# MC21R01_EtherCAT.net
KiCad netlist of a schematic drawn in Altium Designer
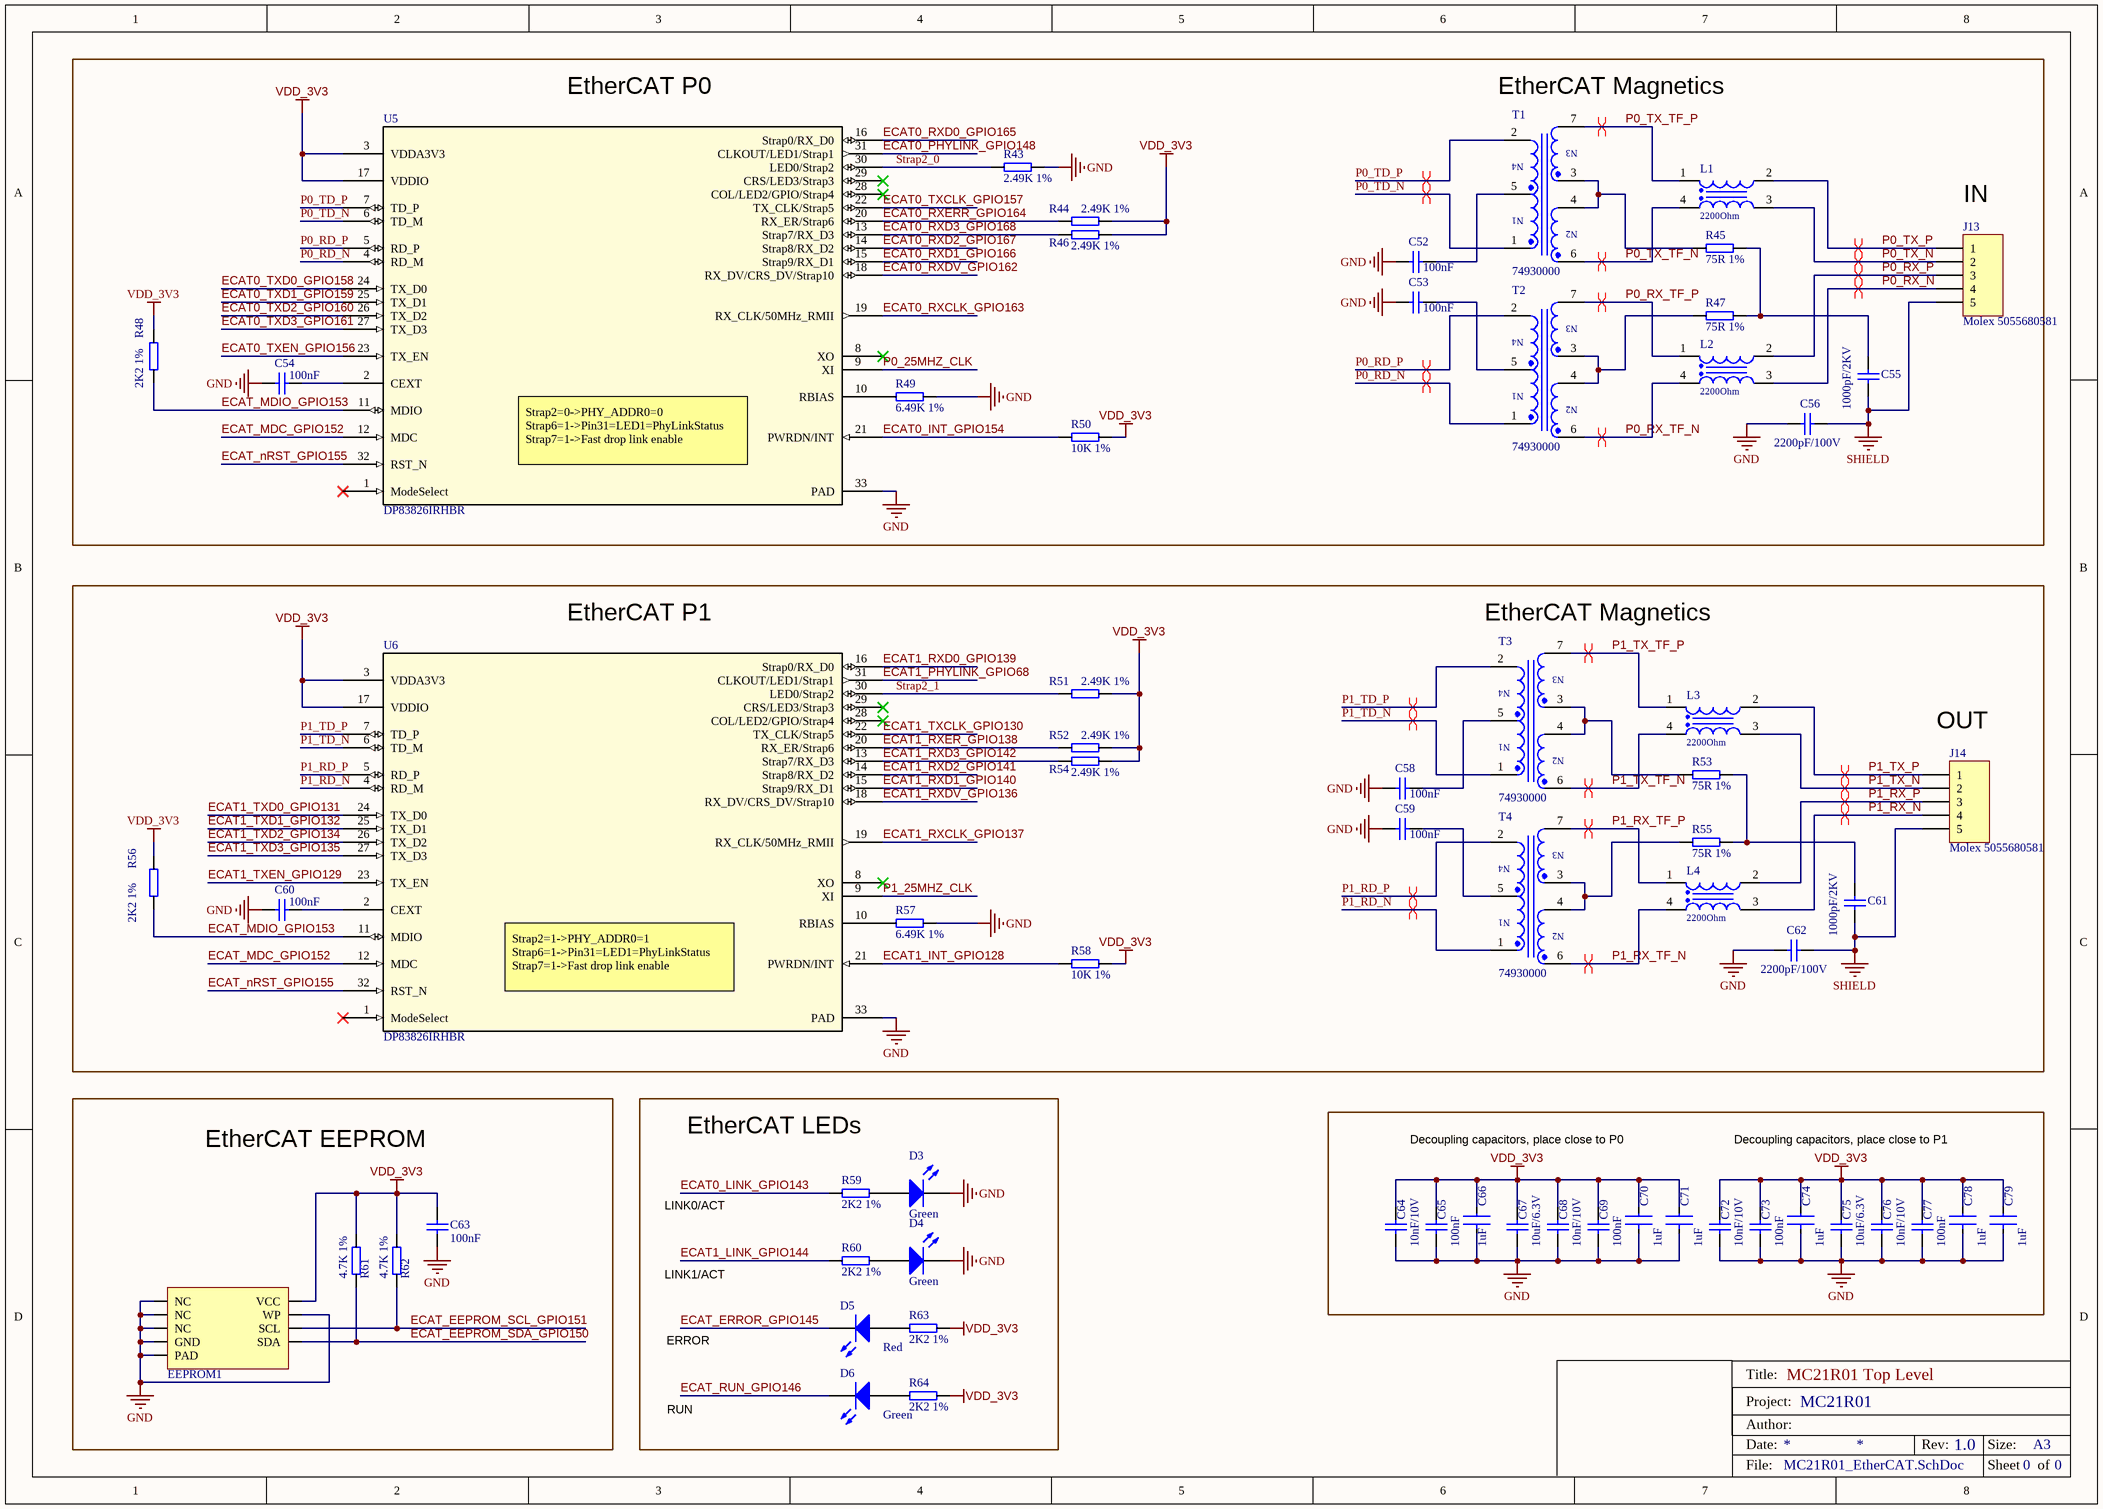
[diagram p0: MC21R01_EtherCAT.SchDoc]

(export (version "E")
  (design (tool "Eeschema 10.0.6"))
  (components
    (comp (ref "C52")
      (value "100nF")
      (footprint "CAPC0603X03N")
      (description "100nF/25V 0201 10% Tolerance X6S Multilayer Ceramic Chip Capacitor")
      (fields (field (name "TOLERANCE") "10%") (field (name "Comment") "100nF/25V 0201 10% X6S"))
      (libsource (lib "Wandercraft") (part "STD_CAP_2PIN_NPOL"))
    )
    (comp (ref "C53")
      (value "100nF")
      (footprint "CAPC0603X03N")
      (description "100nF/25V 0201 10% Tolerance X6S Multilayer Ceramic Chip Capacitor")
      (fields (field (name "TOLERANCE") "10%") (field (name "Comment") "100nF/25V 0201 10% X6S"))
      (libsource (lib "Wandercraft") (part "STD_CAP_2PIN_NPOL"))
    )
    (comp (ref "C54")
      (value "100nF")
      (footprint "CAPC0603X03N")
      (description "100nF/25V 0201 10% Tolerance X6S Multilayer Ceramic Chip Capacitor")
      (fields (field (name "TOLERANCE") "10%") (field (name "Comment") "100nF/25V 0201 10% X6S"))
      (libsource (lib "Wandercraft") (part "STD_CAP_2PIN_NPOL"))
    )
    (comp (ref "C55")
      (value "1000pF/2KV")
      (footprint "PAL_Capacitors:1206 SMD Capacitor")
      (description "1000 pF 2 KV 1206  ±10% Tolerance X7R Multilayer Ceramic Chip Capacitor")
      (libsource (lib "PAL_Capacitors") (part "1000pF/2KV 1206 10% X7R"))
    )
    (comp (ref "C56")
      (value "2200pF/100V")
      (footprint "PAL_Capacitors:0402 SMD Capacitor")
      (description "2200pF/100V 0402 10% Tolerance X7S Multilayer Ceramic Chip Capacitor")
      (fields (field (name "Comment") "2200pF/100V 0402 10% X7S"))
      (libsource (lib "PAL_Capacitors") (part "2200pF/100V 0402 10% X7S"))
    )
    (comp (ref "C58")
      (value "100nF")
      (footprint "CAPC0603X03N")
      (description "100nF/25V 0201 10% Tolerance X6S Multilayer Ceramic Chip Capacitor")
      (fields (field (name "TOLERANCE") "10%") (field (name "Comment") "100nF/25V 0201 10% X6S"))
      (libsource (lib "Wandercraft") (part "STD_CAP_2PIN_NPOL"))
    )
    (comp (ref "C59")
      (value "100nF")
      (footprint "CAPC0603X03N")
      (description "100nF/25V 0201 10% Tolerance X6S Multilayer Ceramic Chip Capacitor")
      (fields (field (name "TOLERANCE") "10%") (field (name "Comment") "100nF/25V 0201 10% X6S"))
      (libsource (lib "Wandercraft") (part "STD_CAP_2PIN_NPOL"))
    )
    (comp (ref "C60")
      (value "100nF")
      (footprint "CAPC0603X03N")
      (description "100nF/25V 0201 10% Tolerance X6S Multilayer Ceramic Chip Capacitor")
      (fields (field (name "TOLERANCE") "10%") (field (name "Comment") "100nF/25V 0201 10% X6S"))
      (libsource (lib "Wandercraft") (part "STD_CAP_2PIN_NPOL"))
    )
    (comp (ref "C61")
      (value "1000pF/2KV")
      (footprint "PAL_Capacitors:1206 SMD Capacitor")
      (description "1000 pF 2 KV 1206  ±10% Tolerance X7R Multilayer Ceramic Chip Capacitor")
      (libsource (lib "PAL_Capacitors") (part "1000pF/2KV 1206 10% X7R"))
    )
    (comp (ref "C62")
      (value "2200pF/100V")
      (footprint "PAL_Capacitors:0402 SMD Capacitor")
      (description "2200pF/100V 0402 10% Tolerance X7S Multilayer Ceramic Chip Capacitor")
      (fields (field (name "Comment") "2200pF/100V 0402 10% X7S"))
      (libsource (lib "PAL_Capacitors") (part "2200pF/100V 0402 10% X7S"))
    )
    (comp (ref "C63")
      (value "100nF")
      (footprint "CAPC0603X03N")
      (description "100nF/25V 0201 10% Tolerance X6S Multilayer Ceramic Chip Capacitor")
      (fields (field (name "TOLERANCE") "10%") (field (name "Comment") "100nF/25V 0201 10% X6S"))
      (libsource (lib "Wandercraft") (part "STD_CAP_2PIN_NPOL"))
    )
    (comp (ref "C64")
      (value "10nF/10V")
      (footprint "PAL_Capacitors:0402 SMD Capacitor")
      (description "10nF/10V 0402 20% Tolerance X5R Multilayer Ceramic Chip Capacitor")
      (fields (field (name "Comment") "10nF/10V 0402 20% X5R"))
      (libsource (lib "PAL_Capacitors") (part "10nF/10V 0402 20% X5R"))
    )
    (comp (ref "C65")
      (value "100nF")
      (footprint "CAPC0603X03N")
      (description "100nF/25V 0201 10% Tolerance X6S Multilayer Ceramic Chip Capacitor")
      (fields (field (name "TOLERANCE") "10%") (field (name "Comment") "100nF/25V 0201 10% X6S"))
      (libsource (lib "Wandercraft") (part "STD_CAP_2PIN_NPOL"))
    )
    (comp (ref "C66")
      (value "1uF/6.3V 0201 10% X5R")
      (footprint "FP-CL03-IPC_A")
      (description "1uF/6.3V 0201 10% Tolerance X5R Multilayer Ceramic Chip Capacitor")
      (fields (field (name "TOLERANCE") "20%") (field (name "CAPACITANCE") "1uF"))
      (libsource (lib "Altium Content Vault") (part "b4654b650e69147ec39a6b967a45e02"))
    )
    (comp (ref "C67")
      (value "10uF/6.3V")
      (footprint "PAL_Capacitors:0402 SMD Capacitor")
      (description "10uF/6.3V 0402 20% Tolerance X5R Multilayer Ceramic Chip Capacitor")
      (fields (field (name "Comment") "10uF/6.3V 0402 20% X5R"))
      (libsource (lib "PAL_Capacitors") (part "10uF/6.3V 0402 20% X5R"))
    )
    (comp (ref "C68")
      (value "10nF/10V")
      (footprint "PAL_Capacitors:0402 SMD Capacitor")
      (description "10nF/10V 0402 20% Tolerance X5R Multilayer Ceramic Chip Capacitor")
      (fields (field (name "Comment") "10nF/10V 0402 20% X5R"))
      (libsource (lib "PAL_Capacitors") (part "10nF/10V 0402 20% X5R"))
    )
    (comp (ref "C69")
      (value "100nF")
      (footprint "CAPC0603X03N")
      (description "100nF/25V 0201 10% Tolerance X6S Multilayer Ceramic Chip Capacitor")
      (fields (field (name "TOLERANCE") "10%") (field (name "Comment") "100nF/25V 0201 10% X6S"))
      (libsource (lib "Wandercraft") (part "STD_CAP_2PIN_NPOL"))
    )
    (comp (ref "C70")
      (value "1uF/6.3V 0201 10% X5R")
      (footprint "FP-CL03-IPC_A")
      (description "1uF/6.3V 0201 10% Tolerance X5R Multilayer Ceramic Chip Capacitor")
      (fields (field (name "TOLERANCE") "20%") (field (name "CAPACITANCE") "1uF"))
      (libsource (lib "Altium Content Vault") (part "b4654b650e69147ec39a6b967a45e02"))
    )
    (comp (ref "C71")
      (value "1uF/6.3V 0201 10% X5R")
      (footprint "FP-CL03-IPC_A")
      (description "1uF/6.3V 0201 10% Tolerance X5R Multilayer Ceramic Chip Capacitor")
      (fields (field (name "TOLERANCE") "20%") (field (name "CAPACITANCE") "1uF"))
      (libsource (lib "Altium Content Vault") (part "b4654b650e69147ec39a6b967a45e02"))
    )
    (comp (ref "C72")
      (value "10nF/10V")
      (footprint "PAL_Capacitors:0402 SMD Capacitor")
      (description "10nF/10V 0402 20% Tolerance X5R Multilayer Ceramic Chip Capacitor")
      (fields (field (name "Comment") "10nF/10V 0402 20% X5R"))
      (libsource (lib "PAL_Capacitors") (part "10nF/10V 0402 20% X5R"))
    )
    (comp (ref "C73")
      (value "100nF")
      (footprint "CAPC0603X03N")
      (description "100nF/25V 0201 10% Tolerance X6S Multilayer Ceramic Chip Capacitor")
      (fields (field (name "TOLERANCE") "10%") (field (name "Comment") "100nF/25V 0201 10% X6S"))
      (libsource (lib "Wandercraft") (part "STD_CAP_2PIN_NPOL"))
    )
    (comp (ref "C74")
      (value "1uF/6.3V 0201 10% X5R")
      (footprint "FP-CL03-IPC_A")
      (description "1uF/6.3V 0201 10% Tolerance X5R Multilayer Ceramic Chip Capacitor")
      (fields (field (name "TOLERANCE") "20%") (field (name "CAPACITANCE") "1uF"))
      (libsource (lib "Altium Content Vault") (part "b4654b650e69147ec39a6b967a45e02"))
    )
    (comp (ref "C75")
      (value "10uF/6.3V")
      (footprint "PAL_Capacitors:0402 SMD Capacitor")
      (description "10uF/6.3V 0402 20% Tolerance X5R Multilayer Ceramic Chip Capacitor")
      (fields (field (name "Comment") "10uF/6.3V 0402 20% X5R"))
      (libsource (lib "PAL_Capacitors") (part "10uF/6.3V 0402 20% X5R"))
    )
    (comp (ref "C76")
      (value "10nF/10V")
      (footprint "PAL_Capacitors:0402 SMD Capacitor")
      (description "10nF/10V 0402 20% Tolerance X5R Multilayer Ceramic Chip Capacitor")
      (fields (field (name "Comment") "10nF/10V 0402 20% X5R"))
      (libsource (lib "PAL_Capacitors") (part "10nF/10V 0402 20% X5R"))
    )
    (comp (ref "C77")
      (value "100nF")
      (footprint "CAPC0603X03N")
      (description "100nF/25V 0201 10% Tolerance X6S Multilayer Ceramic Chip Capacitor")
      (fields (field (name "TOLERANCE") "10%") (field (name "Comment") "100nF/25V 0201 10% X6S"))
      (libsource (lib "Wandercraft") (part "STD_CAP_2PIN_NPOL"))
    )
    (comp (ref "C78")
      (value "1uF/6.3V 0201 10% X5R")
      (footprint "FP-CL03-IPC_A")
      (description "1uF/6.3V 0201 10% Tolerance X5R Multilayer Ceramic Chip Capacitor")
      (fields (field (name "TOLERANCE") "20%") (field (name "CAPACITANCE") "1uF"))
      (libsource (lib "Altium Content Vault") (part "b4654b650e69147ec39a6b967a45e02"))
    )
    (comp (ref "C79")
      (value "1uF/6.3V 0201 10% X5R")
      (footprint "FP-CL03-IPC_A")
      (description "1uF/6.3V 0201 10% Tolerance X5R Multilayer Ceramic Chip Capacitor")
      (fields (field (name "TOLERANCE") "20%") (field (name "CAPACITANCE") "1uF"))
      (libsource (lib "Altium Content Vault") (part "b4654b650e69147ec39a6b967a45e02"))
    )
    (comp (ref "D3")
      (value "Green")
      (footprint "0402 SMD LED GREEN")
      (description "Low Profile Chip LED, Green")
      (fields (field (name "MANUFACTURER") "ROHM") (field (name "MANUFACTURER PART NUMBER") "SML-P11MTT86R"))
      (libsource (lib "PAL_devices") (part "LED_0402_green"))
    )
    (comp (ref "D4")
      (value "Green")
      (footprint "0402 SMD LED GREEN")
      (description "Low Profile Chip LED, Green")
      (fields (field (name "MANUFACTURER") "ROHM") (field (name "MANUFACTURER PART NUMBER") "SML-P11MTT86R"))
      (libsource (lib "PAL_devices") (part "LED_0402_green"))
    )
    (comp (ref "D5")
      (value "Red")
      (footprint "0402 SMD LED Red")
      (description "Low Profile Chip LED, Red")
      (fields (field (name "MANUFACTURER") "ROHM") (field (name "MANUFACTURER PART NUMBER") "SML-P11UTT86R"))
      (libsource (lib "PAL_devices") (part "LED_0402_Red"))
    )
    (comp (ref "D6")
      (value "Green")
      (footprint "0402 SMD LED GREEN")
      (description "Low Profile Chip LED, Green")
      (fields (field (name "MANUFACTURER") "ROHM") (field (name "MANUFACTURER PART NUMBER") "SML-P11MTT86R"))
      (libsource (lib "PAL_devices") (part "LED_0402_green"))
    )
    (comp (ref "EEPROM1")
      (value "CAT24C16HU4I-GT3")
      (footprint "PAL_IPC-7351_2020 :PQFN50P300X200X50_HS-9N")
      (description "CAT24C16 Series 16 Kb (2K x 8) 400 kHz I2C CMOS Serial EEPROM - UDFN-8EP")
      (fields (field (name "MANUFACTURER") "ON Semi") (field (name "CREATED BY") "AMP"))
      (libsource (lib "PAL_Memory_2020") (part "CAT24C16HU4I-GT3"))
    )
    (comp (ref "J13")
      (value "Molex 5055680581")
      (footprint "PAL_Molex_Micro-Lock_2020:Molex 5055680581")
      (fields
        (field (name "MANUFACTURER") "Molex")
        (field (name "MANUFACTURER PART NUMBER") "5055680581")
        (field (name "MATING PART NUMBER") "Molex 5055650501")
        (field (name "CREATED BY") "AMP")
      )
      (libsource (lib "PAL_Molex_Micro-Lock_2020") (part "Molex 5055680581"))
    )
    (comp (ref "J14")
      (value "Molex 5055680581")
      (footprint "PAL_Molex_Micro-Lock_2020:Molex 5055680581")
      (fields
        (field (name "MANUFACTURER") "Molex")
        (field (name "MANUFACTURER PART NUMBER") "5055680581")
        (field (name "MATING PART NUMBER") "Molex 5055650501")
        (field (name "CREATED BY") "AMP")
      )
      (libsource (lib "PAL_Molex_Micro-Lock_2020") (part "Molex 5055680581"))
    )
    (comp (ref "L1")
      (value "2200Ohm")
      (footprint "PAL_Wurth:744232222")
      (description "WE-CNSW SMT Common Mode Line Filter, size 1206, 2200Ohm, 0.2A, 50V")
      (fields
        (field (name "MANUFACTURER PART NUMBER") "744232222")
        (field (name "MANUFACTURER") "Wurth Elektronik")
      )
      (libsource (lib "PAL_Wurth") (part "744232222"))
    )
    (comp (ref "L2")
      (value "2200Ohm")
      (footprint "PAL_Wurth:744232222")
      (description "WE-CNSW SMT Common Mode Line Filter, size 1206, 2200Ohm, 0.2A, 50V")
      (fields
        (field (name "MANUFACTURER PART NUMBER") "744232222")
        (field (name "MANUFACTURER") "Wurth Elektronik")
      )
      (libsource (lib "PAL_Wurth") (part "744232222"))
    )
    (comp (ref "L3")
      (value "2200Ohm")
      (footprint "PAL_Wurth:744232222")
      (description "WE-CNSW SMT Common Mode Line Filter, size 1206, 2200Ohm, 0.2A, 50V")
      (fields
        (field (name "MANUFACTURER PART NUMBER") "744232222")
        (field (name "MANUFACTURER") "Wurth Elektronik")
      )
      (libsource (lib "PAL_Wurth") (part "744232222"))
    )
    (comp (ref "L4")
      (value "2200Ohm")
      (footprint "PAL_Wurth:744232222")
      (description "WE-CNSW SMT Common Mode Line Filter, size 1206, 2200Ohm, 0.2A, 50V")
      (fields
        (field (name "MANUFACTURER PART NUMBER") "744232222")
        (field (name "MANUFACTURER") "Wurth Elektronik")
      )
      (libsource (lib "PAL_Wurth") (part "744232222"))
    )
    (comp (ref "R43")
      (value "2.49K 1%")
      (footprint "0402 SMD rESISTOR")
      (description "2.49K/50V 1% 0402 100mW SMD Resistor")
      (libsource (lib "PAL_Resistors") (part "2.49K/50V 1% 0402 100mW"))
    )
    (comp (ref "R44")
      (value "2.49K 1%")
      (footprint "0402 SMD rESISTOR")
      (description "2.49K/50V 1% 0402 100mW SMD Resistor")
      (libsource (lib "PAL_Resistors") (part "2.49K/50V 1% 0402 100mW"))
    )
    (comp (ref "R45")
      (value "75R 1%")
      (footprint "0402 SMD rESISTOR")
      (description "75R/50V 1% 0402 100mW SMD Resistor")
      (libsource (lib "PAL_Resistors") (part "75R/50V 1% 0402 100mW"))
    )
    (comp (ref "R46")
      (value "2.49K 1%")
      (footprint "0402 SMD rESISTOR")
      (description "2.49K/50V 1% 0402 100mW SMD Resistor")
      (libsource (lib "PAL_Resistors") (part "2.49K/50V 1% 0402 100mW"))
    )
    (comp (ref "R47")
      (value "75R 1%")
      (footprint "0402 SMD rESISTOR")
      (description "75R/50V 1% 0402 100mW SMD Resistor")
      (libsource (lib "PAL_Resistors") (part "75R/50V 1% 0402 100mW"))
    )
    (comp (ref "R48")
      (value "2K2 1%")
      (footprint "0402 SMD rESISTOR")
      (description "2K2/50V 1% 0402 100mW SMD Resistor")
      (libsource (lib "PAL_Resistors") (part "2K2/50V 1% 0402 100mW"))
    )
    (comp (ref "R49")
      (value "6.49K 1%")
      (footprint "0402 SMD rESISTOR")
      (description "6.49K/50V 1% 0402 100mW SMD Resistor")
      (libsource (lib "PAL_Resistors") (part "6.49K/50V 1% 0402 100mW"))
    )
    (comp (ref "R50")
      (value "10K 1%")
      (footprint "0402 SMD rESISTOR")
      (description "10K/50V 1% 0402 100mW SMD Resistor")
      (libsource (lib "PAL_Resistors") (part "10K/50V 1% 0402 100mW"))
    )
    (comp (ref "R51")
      (value "2.49K 1%")
      (footprint "0402 SMD rESISTOR")
      (description "2.49K/50V 1% 0402 100mW SMD Resistor")
      (libsource (lib "PAL_Resistors") (part "2.49K/50V 1% 0402 100mW"))
    )
    (comp (ref "R52")
      (value "2.49K 1%")
      (footprint "0402 SMD rESISTOR")
      (description "2.49K/50V 1% 0402 100mW SMD Resistor")
      (libsource (lib "PAL_Resistors") (part "2.49K/50V 1% 0402 100mW"))
    )
    (comp (ref "R53")
      (value "75R 1%")
      (footprint "0402 SMD rESISTOR")
      (description "75R/50V 1% 0402 100mW SMD Resistor")
      (libsource (lib "PAL_Resistors") (part "75R/50V 1% 0402 100mW"))
    )
    (comp (ref "R54")
      (value "2.49K 1%")
      (footprint "0402 SMD rESISTOR")
      (description "2.49K/50V 1% 0402 100mW SMD Resistor")
      (libsource (lib "PAL_Resistors") (part "2.49K/50V 1% 0402 100mW"))
    )
    (comp (ref "R55")
      (value "75R 1%")
      (footprint "0402 SMD rESISTOR")
      (description "75R/50V 1% 0402 100mW SMD Resistor")
      (libsource (lib "PAL_Resistors") (part "75R/50V 1% 0402 100mW"))
    )
    (comp (ref "R56")
      (value "2K2 1%")
      (footprint "0402 SMD rESISTOR")
      (description "2K2/50V 1% 0402 100mW SMD Resistor")
      (libsource (lib "PAL_Resistors") (part "2K2/50V 1% 0402 100mW"))
    )
    (comp (ref "R57")
      (value "6.49K 1%")
      (footprint "0402 SMD rESISTOR")
      (description "6.49K/50V 1% 0402 100mW SMD Resistor")
      (libsource (lib "PAL_Resistors") (part "6.49K/50V 1% 0402 100mW"))
    )
    (comp (ref "R58")
      (value "10K 1%")
      (footprint "0402 SMD rESISTOR")
      (description "10K/50V 1% 0402 100mW SMD Resistor")
      (libsource (lib "PAL_Resistors") (part "10K/50V 1% 0402 100mW"))
    )
    (comp (ref "R59")
      (value "2K2 1%")
      (footprint "0402 SMD rESISTOR")
      (description "2K2/50V 1% 0402 100mW SMD Resistor")
      (libsource (lib "PAL_Resistors") (part "2K2/50V 1% 0402 100mW"))
    )
    (comp (ref "R60")
      (value "2K2 1%")
      (footprint "0402 SMD rESISTOR")
      (description "2K2/50V 1% 0402 100mW SMD Resistor")
      (libsource (lib "PAL_Resistors") (part "2K2/50V 1% 0402 100mW"))
    )
    (comp (ref "R61")
      (value "4.7K 1%")
      (footprint "0402 SMD rESISTOR")
      (description "4.7K/50V 1% 0402 100mW SMD Resistor")
      (libsource (lib "PAL_Resistors") (part "4.7K/50V 1% 0402 100mW"))
    )
    (comp (ref "R62")
      (value "4.7K 1%")
      (footprint "0402 SMD rESISTOR")
      (description "4.7K/50V 1% 0402 100mW SMD Resistor")
      (libsource (lib "PAL_Resistors") (part "4.7K/50V 1% 0402 100mW"))
    )
    (comp (ref "R63")
      (value "2K2 1%")
      (footprint "0402 SMD rESISTOR")
      (description "2K2/50V 1% 0402 100mW SMD Resistor")
      (libsource (lib "PAL_Resistors") (part "2K2/50V 1% 0402 100mW"))
    )
    (comp (ref "R64")
      (value "2K2 1%")
      (footprint "0402 SMD rESISTOR")
      (description "2K2/50V 1% 0402 100mW SMD Resistor")
      (libsource (lib "PAL_Resistors") (part "2K2/50V 1% 0402 100mW"))
    )
    (comp (ref "T1")
      (value "74930000")
      (footprint "PAL_Wurth:74930000")
      (description "WE-STST Super Tiny Signal Transformer, size 4532, 350uH")
      (fields (field (name "PUBLISHER") "Wurth Elektronik"))
      (libsource (lib "PAL_Wurth") (part "74930000"))
    )
    (comp (ref "T2")
      (value "74930000")
      (footprint "PAL_Wurth:74930000")
      (description "WE-STST Super Tiny Signal Transformer, size 4532, 350uH")
      (fields (field (name "PUBLISHER") "Wurth Elektronik"))
      (libsource (lib "PAL_Wurth") (part "74930000"))
    )
    (comp (ref "T3")
      (value "74930000")
      (footprint "PAL_Wurth:74930000")
      (description "WE-STST Super Tiny Signal Transformer, size 4532, 350uH")
      (fields (field (name "PUBLISHER") "Wurth Elektronik"))
      (libsource (lib "PAL_Wurth") (part "74930000"))
    )
    (comp (ref "T4")
      (value "74930000")
      (footprint "PAL_Wurth:74930000")
      (description "WE-STST Super Tiny Signal Transformer, size 4532, 350uH")
      (fields (field (name "PUBLISHER") "Wurth Elektronik"))
      (libsource (lib "PAL_Wurth") (part "74930000"))
    )
    (comp (ref "U5")
      (value "DP83826IRHBR")
      (footprint "RHB0032B")
      (fields (field (name "MANUFACTURER") "Texas Instruments"))
      (libsource (lib "TI-DP8382x") (part "DP83826IRHBR"))
    )
    (comp (ref "U6")
      (value "DP83826IRHBR")
      (footprint "RHB0032B")
      (fields (field (name "MANUFACTURER") "Texas Instruments"))
      (libsource (lib "TI-DP8382x") (part "DP83826IRHBR"))
    )
  )
  (nets
    (net (code "1") (name "/ECAT0_INT_GPIO154") (class "Default")
      (node (ref "R50") (pin "2") (pinfunction "2_2") (pintype "passive"))
      (node (ref "U5") (pin "21") (pinfunction "PWRDN/INT_21") (pintype "input"))
    )
    (net (code "2") (name "/ECAT0_LINK_GPIO143") (class "Default")
      (node (ref "R59") (pin "2") (pinfunction "2_2") (pintype "passive"))
    )
    (net (code "3") (name "/ECAT0_PHYLINK_GPIO148") (class "Default")
      (node (ref "U5") (pin "31") (pinfunction "CLKOUT/LED1/Strap1_31") (pintype "output"))
    )
    (net (code "4") (name "/ECAT0_RXCLK_GPIO163") (class "Default")
      (node (ref "U5") (pin "19") (pinfunction "RX_CLK/50MHz_RMII_19") (pintype "output"))
    )
    (net (code "5") (name "/ECAT0_RXD0_GPIO165") (class "Default")
      (node (ref "U5") (pin "16") (pinfunction "Strap0/RX_D0_16") (pintype "bidirectional"))
    )
    (net (code "6") (name "/ECAT0_RXD1_GPIO166") (class "Default")
      (node (ref "U5") (pin "15") (pinfunction "Strap9/RX_D1_15") (pintype "bidirectional"))
    )
    (net (code "7") (name "/ECAT0_RXD2_GPIO167") (class "Default")
      (node (ref "U5") (pin "14") (pinfunction "Strap8/RX_D2_14") (pintype "bidirectional"))
    )
    (net (code "8") (name "/ECAT0_RXD3_GPIO168") (class "Default")
      (node (ref "R46") (pin "1") (pinfunction "1_1") (pintype "passive"))
      (node (ref "U5") (pin "13") (pinfunction "Strap7/RX_D3_13") (pintype "bidirectional"))
    )
    (net (code "9") (name "/ECAT0_RXDV_GPIO162") (class "Default")
      (node (ref "U5") (pin "18") (pinfunction "RX_DV/CRS_DV/Strap10_18") (pintype "bidirectional"))
    )
    (net (code "10") (name "/ECAT0_RXERR_GPIO164") (class "Default")
      (node (ref "R44") (pin "2") (pinfunction "2_2") (pintype "passive"))
      (node (ref "U5") (pin "20") (pinfunction "RX_ER/Strap6_20") (pintype "bidirectional"))
    )
    (net (code "11") (name "/ECAT0_TXCLK_GPIO157") (class "Default")
      (node (ref "U5") (pin "22") (pinfunction "TX_CLK/Strap5_22") (pintype "bidirectional"))
    )
    (net (code "12") (name "/ECAT0_TXD0_GPIO158") (class "Default")
      (node (ref "U5") (pin "24") (pinfunction "TX_D0_24") (pintype "input"))
    )
    (net (code "13") (name "/ECAT0_TXD1_GPIO159") (class "Default")
      (node (ref "U5") (pin "25") (pinfunction "TX_D1_25") (pintype "input"))
    )
    (net (code "14") (name "/ECAT0_TXD2_GPIO160") (class "Default")
      (node (ref "U5") (pin "26") (pinfunction "TX_D2_26") (pintype "input"))
    )
    (net (code "15") (name "/ECAT0_TXD3_GPIO161") (class "Default")
      (node (ref "U5") (pin "27") (pinfunction "TX_D3_27") (pintype "input"))
    )
    (net (code "16") (name "/ECAT0_TXEN_GPIO156") (class "Default")
      (node (ref "U5") (pin "23") (pinfunction "TX_EN_23") (pintype "input"))
    )
    (net (code "17") (name "/ECAT1_INT_GPIO128") (class "Default")
      (node (ref "R58") (pin "2") (pinfunction "2_2") (pintype "passive"))
      (node (ref "U6") (pin "21") (pinfunction "PWRDN/INT_21") (pintype "input"))
    )
    (net (code "18") (name "/ECAT1_LINK_GPIO144") (class "Default")
      (node (ref "R60") (pin "2") (pinfunction "2_2") (pintype "passive"))
    )
    (net (code "19") (name "/ECAT1_PHYLINK_GPIO68") (class "Default")
      (node (ref "U6") (pin "31") (pinfunction "CLKOUT/LED1/Strap1_31") (pintype "output"))
    )
    (net (code "20") (name "/ECAT1_RXCLK_GPIO137") (class "Default")
      (node (ref "U6") (pin "19") (pinfunction "RX_CLK/50MHz_RMII_19") (pintype "output"))
    )
    (net (code "21") (name "/ECAT1_RXD0_GPIO139") (class "Default")
      (node (ref "U6") (pin "16") (pinfunction "Strap0/RX_D0_16") (pintype "bidirectional"))
    )
    (net (code "22") (name "/ECAT1_RXD1_GPIO140") (class "Default")
      (node (ref "U6") (pin "15") (pinfunction "Strap9/RX_D1_15") (pintype "bidirectional"))
    )
    (net (code "23") (name "/ECAT1_RXD2_GPIO141") (class "Default")
      (node (ref "U6") (pin "14") (pinfunction "Strap8/RX_D2_14") (pintype "bidirectional"))
    )
    (net (code "24") (name "/ECAT1_RXD3_GPIO142") (class "Default")
      (node (ref "R54") (pin "1") (pinfunction "1_1") (pintype "passive"))
      (node (ref "U6") (pin "13") (pinfunction "Strap7/RX_D3_13") (pintype "bidirectional"))
    )
    (net (code "25") (name "/ECAT1_RXDV_GPIO136") (class "Default")
      (node (ref "U6") (pin "18") (pinfunction "RX_DV/CRS_DV/Strap10_18") (pintype "bidirectional"))
    )
    (net (code "26") (name "/ECAT1_RXER_GPIO138") (class "Default")
      (node (ref "R52") (pin "2") (pinfunction "2_2") (pintype "passive"))
      (node (ref "U6") (pin "20") (pinfunction "RX_ER/Strap6_20") (pintype "bidirectional"))
    )
    (net (code "27") (name "/ECAT1_TXCLK_GPIO130") (class "Default")
      (node (ref "U6") (pin "22") (pinfunction "TX_CLK/Strap5_22") (pintype "bidirectional"))
    )
    (net (code "28") (name "/ECAT1_TXD0_GPIO131") (class "Default")
      (node (ref "U6") (pin "24") (pinfunction "TX_D0_24") (pintype "input"))
    )
    (net (code "29") (name "/ECAT1_TXD1_GPIO132") (class "Default")
      (node (ref "U6") (pin "25") (pinfunction "TX_D1_25") (pintype "input"))
    )
    (net (code "30") (name "/ECAT1_TXD2_GPIO134") (class "Default")
      (node (ref "U6") (pin "26") (pinfunction "TX_D2_26") (pintype "input"))
    )
    (net (code "31") (name "/ECAT1_TXD3_GPIO135") (class "Default")
      (node (ref "U6") (pin "27") (pinfunction "TX_D3_27") (pintype "input"))
    )
    (net (code "32") (name "/ECAT1_TXEN_GPIO129") (class "Default")
      (node (ref "U6") (pin "23") (pinfunction "TX_EN_23") (pintype "input"))
    )
    (net (code "33") (name "/ECAT_EEPROM_SCL_GPIO151") (class "Default")
      (node (ref "EEPROM1") (pin "6") (pinfunction "SCL_6") (pintype "passive"))
      (node (ref "R62") (pin "1") (pinfunction "1_1") (pintype "passive"))
    )
    (net (code "34") (name "/ECAT_EEPROM_SDA_GPIO150") (class "Default")
      (node (ref "EEPROM1") (pin "5") (pinfunction "SDA_5") (pintype "passive"))
      (node (ref "R61") (pin "1") (pinfunction "1_1") (pintype "passive"))
    )
    (net (code "35") (name "/ECAT_ERROR_GPIO145") (class "Default")
      (node (ref "D5") (pin "K") (pinfunction "K_K") (pintype "passive"))
    )
    (net (code "36") (name "/ECAT_MDC_GPIO152") (class "Default")
      (node (ref "U5") (pin "12") (pinfunction "MDC_12") (pintype "input"))
      (node (ref "U6") (pin "12") (pinfunction "MDC_12") (pintype "input"))
    )
    (net (code "37") (name "/ECAT_MDIO_GPIO153") (class "Default")
      (node (ref "R48") (pin "1") (pinfunction "1_1") (pintype "passive"))
      (node (ref "R56") (pin "1") (pinfunction "1_1") (pintype "passive"))
      (node (ref "U5") (pin "11") (pinfunction "MDIO_11") (pintype "bidirectional"))
      (node (ref "U6") (pin "11") (pinfunction "MDIO_11") (pintype "bidirectional"))
    )
    (net (code "38") (name "/ECAT_RUN_GPIO146") (class "Default")
      (node (ref "D6") (pin "K") (pinfunction "K_K") (pintype "passive"))
    )
    (net (code "39") (name "/ECAT_nRST_GPIO155") (class "Default")
      (node (ref "U5") (pin "32") (pinfunction "RST_N_32") (pintype "input"))
      (node (ref "U6") (pin "32") (pinfunction "RST_N_32") (pintype "input"))
    )
    (net (code "40") (name "/P0_25MHZ_CLK") (class "Default")
      (node (ref "U5") (pin "9") (pinfunction "XI_9") (pintype "passive"))
    )
    (net (code "41") (name "/P0_RD_N") (class "Default")
      (node (ref "T2") (pin "1") (pinfunction "1_1") (pintype "passive"))
      (node (ref "U5") (pin "4") (pinfunction "RD_M_4") (pintype "bidirectional"))
    )
    (net (code "42") (name "/P0_RD_P") (class "Default")
      (node (ref "T2") (pin "2") (pinfunction "2_2") (pintype "passive"))
      (node (ref "U5") (pin "5") (pinfunction "RD_P_5") (pintype "bidirectional"))
    )
    (net (code "43") (name "/P0_RX_N") (class "Default")
      (node (ref "J13") (pin "4") (pinfunction "4_4") (pintype "passive"))
      (node (ref "L2") (pin "3") (pinfunction "3_3") (pintype "passive"))
    )
    (net (code "44") (name "/P0_RX_P") (class "Default")
      (node (ref "J13") (pin "3") (pinfunction "3_3") (pintype "passive"))
      (node (ref "L2") (pin "2") (pinfunction "2_2") (pintype "passive"))
    )
    (net (code "45") (name "/P0_RX_TF_N") (class "Default")
      (node (ref "L2") (pin "4") (pinfunction "4_4") (pintype "passive"))
      (node (ref "T2") (pin "6") (pinfunction "6_6") (pintype "passive"))
    )
    (net (code "46") (name "/P0_RX_TF_P") (class "Default")
      (node (ref "L2") (pin "1") (pinfunction "1_1") (pintype "passive"))
      (node (ref "T2") (pin "7") (pinfunction "7_7") (pintype "passive"))
    )
    (net (code "47") (name "/P0_TD_N") (class "Default")
      (node (ref "T1") (pin "1") (pinfunction "1_1") (pintype "passive"))
      (node (ref "U5") (pin "6") (pinfunction "TD_M_6") (pintype "bidirectional"))
    )
    (net (code "48") (name "/P0_TD_P") (class "Default")
      (node (ref "T1") (pin "2") (pinfunction "2_2") (pintype "passive"))
      (node (ref "U5") (pin "7") (pinfunction "TD_P_7") (pintype "bidirectional"))
    )
    (net (code "49") (name "/P0_TX_N") (class "Default")
      (node (ref "J13") (pin "2") (pinfunction "2_2") (pintype "passive"))
      (node (ref "L1") (pin "3") (pinfunction "3_3") (pintype "passive"))
    )
    (net (code "50") (name "/P0_TX_P") (class "Default")
      (node (ref "J13") (pin "1") (pinfunction "1_1") (pintype "passive"))
      (node (ref "L1") (pin "2") (pinfunction "2_2") (pintype "passive"))
    )
    (net (code "51") (name "/P0_TX_TF_N") (class "Default")
      (node (ref "L1") (pin "4") (pinfunction "4_4") (pintype "passive"))
      (node (ref "T1") (pin "6") (pinfunction "6_6") (pintype "passive"))
    )
    (net (code "52") (name "/P0_TX_TF_P") (class "Default")
      (node (ref "L1") (pin "1") (pinfunction "1_1") (pintype "passive"))
      (node (ref "T1") (pin "7") (pinfunction "7_7") (pintype "passive"))
    )
    (net (code "53") (name "/P1_25MHZ_CLK") (class "Default")
      (node (ref "U6") (pin "9") (pinfunction "XI_9") (pintype "passive"))
    )
    (net (code "54") (name "/P1_RD_N") (class "Default")
      (node (ref "T4") (pin "1") (pinfunction "1_1") (pintype "passive"))
      (node (ref "U6") (pin "4") (pinfunction "RD_M_4") (pintype "bidirectional"))
    )
    (net (code "55") (name "/P1_RD_P") (class "Default")
      (node (ref "T4") (pin "2") (pinfunction "2_2") (pintype "passive"))
      (node (ref "U6") (pin "5") (pinfunction "RD_P_5") (pintype "bidirectional"))
    )
    (net (code "56") (name "/P1_RX_N") (class "Default")
      (node (ref "J14") (pin "4") (pinfunction "4_4") (pintype "passive"))
      (node (ref "L4") (pin "3") (pinfunction "3_3") (pintype "passive"))
    )
    (net (code "57") (name "/P1_RX_P") (class "Default")
      (node (ref "J14") (pin "3") (pinfunction "3_3") (pintype "passive"))
      (node (ref "L4") (pin "2") (pinfunction "2_2") (pintype "passive"))
    )
    (net (code "58") (name "/P1_RX_TF_N") (class "Default")
      (node (ref "L4") (pin "4") (pinfunction "4_4") (pintype "passive"))
      (node (ref "T4") (pin "6") (pinfunction "6_6") (pintype "passive"))
    )
    (net (code "59") (name "/P1_RX_TF_P") (class "Default")
      (node (ref "L4") (pin "1") (pinfunction "1_1") (pintype "passive"))
      (node (ref "T4") (pin "7") (pinfunction "7_7") (pintype "passive"))
    )
    (net (code "60") (name "/P1_TD_N") (class "Default")
      (node (ref "T3") (pin "1") (pinfunction "1_1") (pintype "passive"))
      (node (ref "U6") (pin "6") (pinfunction "TD_M_6") (pintype "bidirectional"))
    )
    (net (code "61") (name "/P1_TD_P") (class "Default")
      (node (ref "T3") (pin "2") (pinfunction "2_2") (pintype "passive"))
      (node (ref "U6") (pin "7") (pinfunction "TD_P_7") (pintype "bidirectional"))
    )
    (net (code "62") (name "/P1_TX_N") (class "Default")
      (node (ref "J14") (pin "2") (pinfunction "2_2") (pintype "passive"))
      (node (ref "L3") (pin "3") (pinfunction "3_3") (pintype "passive"))
    )
    (net (code "63") (name "/P1_TX_P") (class "Default")
      (node (ref "J14") (pin "1") (pinfunction "1_1") (pintype "passive"))
      (node (ref "L3") (pin "2") (pinfunction "2_2") (pintype "passive"))
    )
    (net (code "64") (name "/P1_TX_TF_N") (class "Default")
      (node (ref "L3") (pin "4") (pinfunction "4_4") (pintype "passive"))
      (node (ref "T3") (pin "6") (pinfunction "6_6") (pintype "passive"))
    )
    (net (code "65") (name "/P1_TX_TF_P") (class "Default")
      (node (ref "L3") (pin "1") (pinfunction "1_1") (pintype "passive"))
      (node (ref "T3") (pin "7") (pinfunction "7_7") (pintype "passive"))
    )
    (net (code "66") (name "/Strap2_0") (class "Default")
      (node (ref "R43") (pin "2") (pinfunction "2_2") (pintype "passive"))
      (node (ref "U5") (pin "30") (pinfunction "LED0/Strap2_30") (pintype "bidirectional"))
    )
    (net (code "67") (name "/Strap2_1") (class "Default")
      (node (ref "R51") (pin "2") (pinfunction "2_2") (pintype "passive"))
      (node (ref "U6") (pin "30") (pinfunction "LED0/Strap2_30") (pintype "bidirectional"))
    )
    (net (code "68") (name "GND") (class "Default")
      (node (ref "C52") (pin "2") (pinfunction "2_2") (pintype "passive"))
      (node (ref "C53") (pin "2") (pinfunction "2_2") (pintype "passive"))
      (node (ref "C54") (pin "1") (pinfunction "1_1") (pintype "passive"))
      (node (ref "C56") (pin "1") (pinfunction "1_1") (pintype "passive"))
      (node (ref "C58") (pin "2") (pinfunction "2_2") (pintype "passive"))
      (node (ref "C59") (pin "2") (pinfunction "2_2") (pintype "passive"))
      (node (ref "C60") (pin "1") (pinfunction "1_1") (pintype "passive"))
      (node (ref "C62") (pin "1") (pinfunction "1_1") (pintype "passive"))
      (node (ref "C63") (pin "1") (pinfunction "1_1") (pintype "passive"))
      (node (ref "C64") (pin "2") (pinfunction "2_2") (pintype "passive"))
      (node (ref "C65") (pin "1") (pinfunction "1_1") (pintype "passive"))
      (node (ref "C66") (pin "1") (pinfunction "1_1") (pintype "passive"))
      (node (ref "C67") (pin "2") (pinfunction "2_2") (pintype "passive"))
      (node (ref "C68") (pin "2") (pinfunction "2_2") (pintype "passive"))
      (node (ref "C69") (pin "1") (pinfunction "1_1") (pintype "passive"))
      (node (ref "C70") (pin "1") (pinfunction "1_1") (pintype "passive"))
      (node (ref "C71") (pin "1") (pinfunction "1_1") (pintype "passive"))
      (node (ref "C72") (pin "2") (pinfunction "2_2") (pintype "passive"))
      (node (ref "C73") (pin "1") (pinfunction "1_1") (pintype "passive"))
      (node (ref "C74") (pin "1") (pinfunction "1_1") (pintype "passive"))
      (node (ref "C75") (pin "2") (pinfunction "2_2") (pintype "passive"))
      (node (ref "C76") (pin "2") (pinfunction "2_2") (pintype "passive"))
      (node (ref "C77") (pin "1") (pinfunction "1_1") (pintype "passive"))
      (node (ref "C78") (pin "1") (pinfunction "1_1") (pintype "passive"))
      (node (ref "C79") (pin "1") (pinfunction "1_1") (pintype "passive"))
      (node (ref "D3") (pin "K") (pinfunction "K_K") (pintype "passive"))
      (node (ref "D4") (pin "K") (pinfunction "K_K") (pintype "passive"))
      (node (ref "EEPROM1") (pin "1") (pinfunction "NC_1") (pintype "passive"))
      (node (ref "EEPROM1") (pin "2") (pinfunction "NC_2") (pintype "passive"))
      (node (ref "EEPROM1") (pin "3") (pinfunction "NC_3") (pintype "passive"))
      (node (ref "EEPROM1") (pin "4") (pinfunction "GND_4") (pintype "passive"))
      (node (ref "EEPROM1") (pin "7") (pinfunction "WP_7") (pintype "passive"))
      (node (ref "EEPROM1") (pin "9") (pinfunction "PAD_9") (pintype "passive"))
      (node (ref "R43") (pin "1") (pinfunction "1_1") (pintype "passive"))
      (node (ref "R49") (pin "2") (pinfunction "2_2") (pintype "passive"))
      (node (ref "R57") (pin "2") (pinfunction "2_2") (pintype "passive"))
      (node (ref "U5") (pin "33") (pinfunction "PAD_33") (pintype "power_in"))
      (node (ref "U6") (pin "33") (pinfunction "PAD_33") (pintype "power_in"))
    )
    (net (code "69") (name "Net-(C52-Pad1)") (class "Default")
      (node (ref "C52") (pin "1") (pinfunction "1_1") (pintype "passive"))
      (node (ref "T1") (pin "5") (pinfunction "5_5") (pintype "passive"))
    )
    (net (code "70") (name "Net-(C53-Pad1)") (class "Default")
      (node (ref "C53") (pin "1") (pinfunction "1_1") (pintype "passive"))
      (node (ref "T2") (pin "5") (pinfunction "5_5") (pintype "passive"))
    )
    (net (code "71") (name "Net-(C55-Pad1)") (class "Default")
      (node (ref "C55") (pin "1") (pinfunction "1_1") (pintype "passive"))
      (node (ref "R45") (pin "1") (pinfunction "1_1") (pintype "passive"))
      (node (ref "R47") (pin "1") (pinfunction "1_1") (pintype "passive"))
    )
    (net (code "72") (name "Net-(C58-Pad1)") (class "Default")
      (node (ref "C58") (pin "1") (pinfunction "1_1") (pintype "passive"))
      (node (ref "T3") (pin "5") (pinfunction "5_5") (pintype "passive"))
    )
    (net (code "73") (name "Net-(C59-Pad1)") (class "Default")
      (node (ref "C59") (pin "1") (pinfunction "1_1") (pintype "passive"))
      (node (ref "T4") (pin "5") (pinfunction "5_5") (pintype "passive"))
    )
    (net (code "74") (name "Net-(C61-Pad1)") (class "Default")
      (node (ref "C61") (pin "1") (pinfunction "1_1") (pintype "passive"))
      (node (ref "R53") (pin "1") (pinfunction "1_1") (pintype "passive"))
      (node (ref "R55") (pin "1") (pinfunction "1_1") (pintype "passive"))
    )
    (net (code "75") (name "Net-(D3-PadA)") (class "Default")
      (node (ref "D3") (pin "A") (pinfunction "A_A") (pintype "passive"))
      (node (ref "R59") (pin "1") (pinfunction "1_1") (pintype "passive"))
    )
    (net (code "76") (name "Net-(D4-PadA)") (class "Default")
      (node (ref "D4") (pin "A") (pinfunction "A_A") (pintype "passive"))
      (node (ref "R60") (pin "1") (pinfunction "1_1") (pintype "passive"))
    )
    (net (code "77") (name "Net-(D5-PadA)") (class "Default")
      (node (ref "D5") (pin "A") (pinfunction "A_A") (pintype "passive"))
      (node (ref "R63") (pin "2") (pinfunction "2_2") (pintype "passive"))
    )
    (net (code "78") (name "Net-(D6-PadA)") (class "Default")
      (node (ref "D6") (pin "A") (pinfunction "A_A") (pintype "passive"))
      (node (ref "R64") (pin "2") (pinfunction "2_2") (pintype "passive"))
    )
    (net (code "79") (name "Net-(R45-Pad2)") (class "Default")
      (node (ref "R45") (pin "2") (pinfunction "2_2") (pintype "passive"))
      (node (ref "T1") (pin "3") (pinfunction "3_3") (pintype "passive"))
      (node (ref "T1") (pin "4") (pinfunction "4_4") (pintype "passive"))
    )
    (net (code "80") (name "Net-(R47-Pad2)") (class "Default")
      (node (ref "R47") (pin "2") (pinfunction "2_2") (pintype "passive"))
      (node (ref "T2") (pin "3") (pinfunction "3_3") (pintype "passive"))
      (node (ref "T2") (pin "4") (pinfunction "4_4") (pintype "passive"))
    )
    (net (code "81") (name "Net-(R53-Pad2)") (class "Default")
      (node (ref "R53") (pin "2") (pinfunction "2_2") (pintype "passive"))
      (node (ref "T3") (pin "3") (pinfunction "3_3") (pintype "passive"))
      (node (ref "T3") (pin "4") (pinfunction "4_4") (pintype "passive"))
    )
    (net (code "82") (name "Net-(R55-Pad2)") (class "Default")
      (node (ref "R55") (pin "2") (pinfunction "2_2") (pintype "passive"))
      (node (ref "T4") (pin "3") (pinfunction "3_3") (pintype "passive"))
      (node (ref "T4") (pin "4") (pinfunction "4_4") (pintype "passive"))
    )
    (net (code "83") (name "Net-(U5-CEXT)") (class "Default")
      (node (ref "C54") (pin "2") (pinfunction "2_2") (pintype "passive"))
      (node (ref "U5") (pin "2") (pinfunction "CEXT_2") (pintype "passive"))
    )
    (net (code "84") (name "Net-(U5-RBIAS)") (class "Default")
      (node (ref "R49") (pin "1") (pinfunction "1_1") (pintype "passive"))
      (node (ref "U5") (pin "10") (pinfunction "RBIAS_10") (pintype "passive"))
    )
    (net (code "85") (name "Net-(U6-CEXT)") (class "Default")
      (node (ref "C60") (pin "2") (pinfunction "2_2") (pintype "passive"))
      (node (ref "U6") (pin "2") (pinfunction "CEXT_2") (pintype "passive"))
    )
    (net (code "86") (name "Net-(U6-RBIAS)") (class "Default")
      (node (ref "R57") (pin "1") (pinfunction "1_1") (pintype "passive"))
      (node (ref "U6") (pin "10") (pinfunction "RBIAS_10") (pintype "passive"))
    )
    (net (code "87") (name "SHIELD") (class "Default")
      (node (ref "C55") (pin "2") (pinfunction "2_2") (pintype "passive"))
      (node (ref "C56") (pin "2") (pinfunction "2_2") (pintype "passive"))
      (node (ref "C61") (pin "2") (pinfunction "2_2") (pintype "passive"))
      (node (ref "C62") (pin "2") (pinfunction "2_2") (pintype "passive"))
      (node (ref "J13") (pin "5") (pinfunction "5_5") (pintype "passive"))
      (node (ref "J14") (pin "5") (pinfunction "5_5") (pintype "passive"))
    )
    (net (code "88") (name "VDD_3V3") (class "Default")
      (node (ref "C63") (pin "2") (pinfunction "2_2") (pintype "passive"))
      (node (ref "C64") (pin "1") (pinfunction "1_1") (pintype "passive"))
      (node (ref "C65") (pin "2") (pinfunction "2_2") (pintype "passive"))
      (node (ref "C66") (pin "2") (pinfunction "2_2") (pintype "passive"))
      (node (ref "C67") (pin "1") (pinfunction "1_1") (pintype "passive"))
      (node (ref "C68") (pin "1") (pinfunction "1_1") (pintype "passive"))
      (node (ref "C69") (pin "2") (pinfunction "2_2") (pintype "passive"))
      (node (ref "C70") (pin "2") (pinfunction "2_2") (pintype "passive"))
      (node (ref "C71") (pin "2") (pinfunction "2_2") (pintype "passive"))
      (node (ref "C72") (pin "1") (pinfunction "1_1") (pintype "passive"))
      (node (ref "C73") (pin "2") (pinfunction "2_2") (pintype "passive"))
      (node (ref "C74") (pin "2") (pinfunction "2_2") (pintype "passive"))
      (node (ref "C75") (pin "1") (pinfunction "1_1") (pintype "passive"))
      (node (ref "C76") (pin "1") (pinfunction "1_1") (pintype "passive"))
      (node (ref "C77") (pin "2") (pinfunction "2_2") (pintype "passive"))
      (node (ref "C78") (pin "2") (pinfunction "2_2") (pintype "passive"))
      (node (ref "C79") (pin "2") (pinfunction "2_2") (pintype "passive"))
      (node (ref "EEPROM1") (pin "8") (pinfunction "VCC_8") (pintype "passive"))
      (node (ref "R44") (pin "1") (pinfunction "1_1") (pintype "passive"))
      (node (ref "R46") (pin "2") (pinfunction "2_2") (pintype "passive"))
      (node (ref "R48") (pin "2") (pinfunction "2_2") (pintype "passive"))
      (node (ref "R50") (pin "1") (pinfunction "1_1") (pintype "passive"))
      (node (ref "R51") (pin "1") (pinfunction "1_1") (pintype "passive"))
      (node (ref "R52") (pin "1") (pinfunction "1_1") (pintype "passive"))
      (node (ref "R54") (pin "2") (pinfunction "2_2") (pintype "passive"))
      (node (ref "R56") (pin "2") (pinfunction "2_2") (pintype "passive"))
      (node (ref "R58") (pin "1") (pinfunction "1_1") (pintype "passive"))
      (node (ref "R61") (pin "2") (pinfunction "2_2") (pintype "passive"))
      (node (ref "R62") (pin "2") (pinfunction "2_2") (pintype "passive"))
      (node (ref "R63") (pin "1") (pinfunction "1_1") (pintype "passive"))
      (node (ref "R64") (pin "1") (pinfunction "1_1") (pintype "passive"))
      (node (ref "U5") (pin "17") (pinfunction "VDDIO_17") (pintype "power_in"))
      (node (ref "U5") (pin "3") (pinfunction "VDDA3V3_3") (pintype "power_in"))
      (node (ref "U6") (pin "17") (pinfunction "VDDIO_17") (pintype "power_in"))
      (node (ref "U6") (pin "3") (pinfunction "VDDA3V3_3") (pintype "power_in"))
    )
    (net (code "89") (name "unconnected-(U5-COL{slash}LED2{slash}GPIO{slash}Strap4-Pad28)") (class "Default")
      (node (ref "U5") (pin "28") (pinfunction "COL/LED2/GPIO/Strap4_28") (pintype "bidirectional+no_connect"))
    )
    (net (code "90") (name "unconnected-(U5-CRS{slash}LED3{slash}Strap3-Pad29)") (class "Default")
      (node (ref "U5") (pin "29") (pinfunction "CRS/LED3/Strap3_29") (pintype "bidirectional+no_connect"))
    )
    (net (code "91") (name "unconnected-(U5-ModeSelect-Pad1)") (class "Default")
      (node (ref "U5") (pin "1") (pinfunction "ModeSelect_1") (pintype "input+no_connect"))
    )
    (net (code "92") (name "unconnected-(U5-XO-Pad8)") (class "Default")
      (node (ref "U5") (pin "8") (pinfunction "XO_8") (pintype "passive+no_connect"))
    )
    (net (code "93") (name "unconnected-(U6-COL{slash}LED2{slash}GPIO{slash}Strap4-Pad28)") (class "Default")
      (node (ref "U6") (pin "28") (pinfunction "COL/LED2/GPIO/Strap4_28") (pintype "bidirectional+no_connect"))
    )
    (net (code "94") (name "unconnected-(U6-CRS{slash}LED3{slash}Strap3-Pad29)") (class "Default")
      (node (ref "U6") (pin "29") (pinfunction "CRS/LED3/Strap3_29") (pintype "bidirectional+no_connect"))
    )
    (net (code "95") (name "unconnected-(U6-ModeSelect-Pad1)") (class "Default")
      (node (ref "U6") (pin "1") (pinfunction "ModeSelect_1") (pintype "input+no_connect"))
    )
    (net (code "96") (name "unconnected-(U6-XO-Pad8)") (class "Default")
      (node (ref "U6") (pin "8") (pinfunction "XO_8") (pintype "passive+no_connect"))
    )
  )
)
